# STM32F103RCT6.net
KiCad netlist of a schematic drawn in EasyEDA Pro
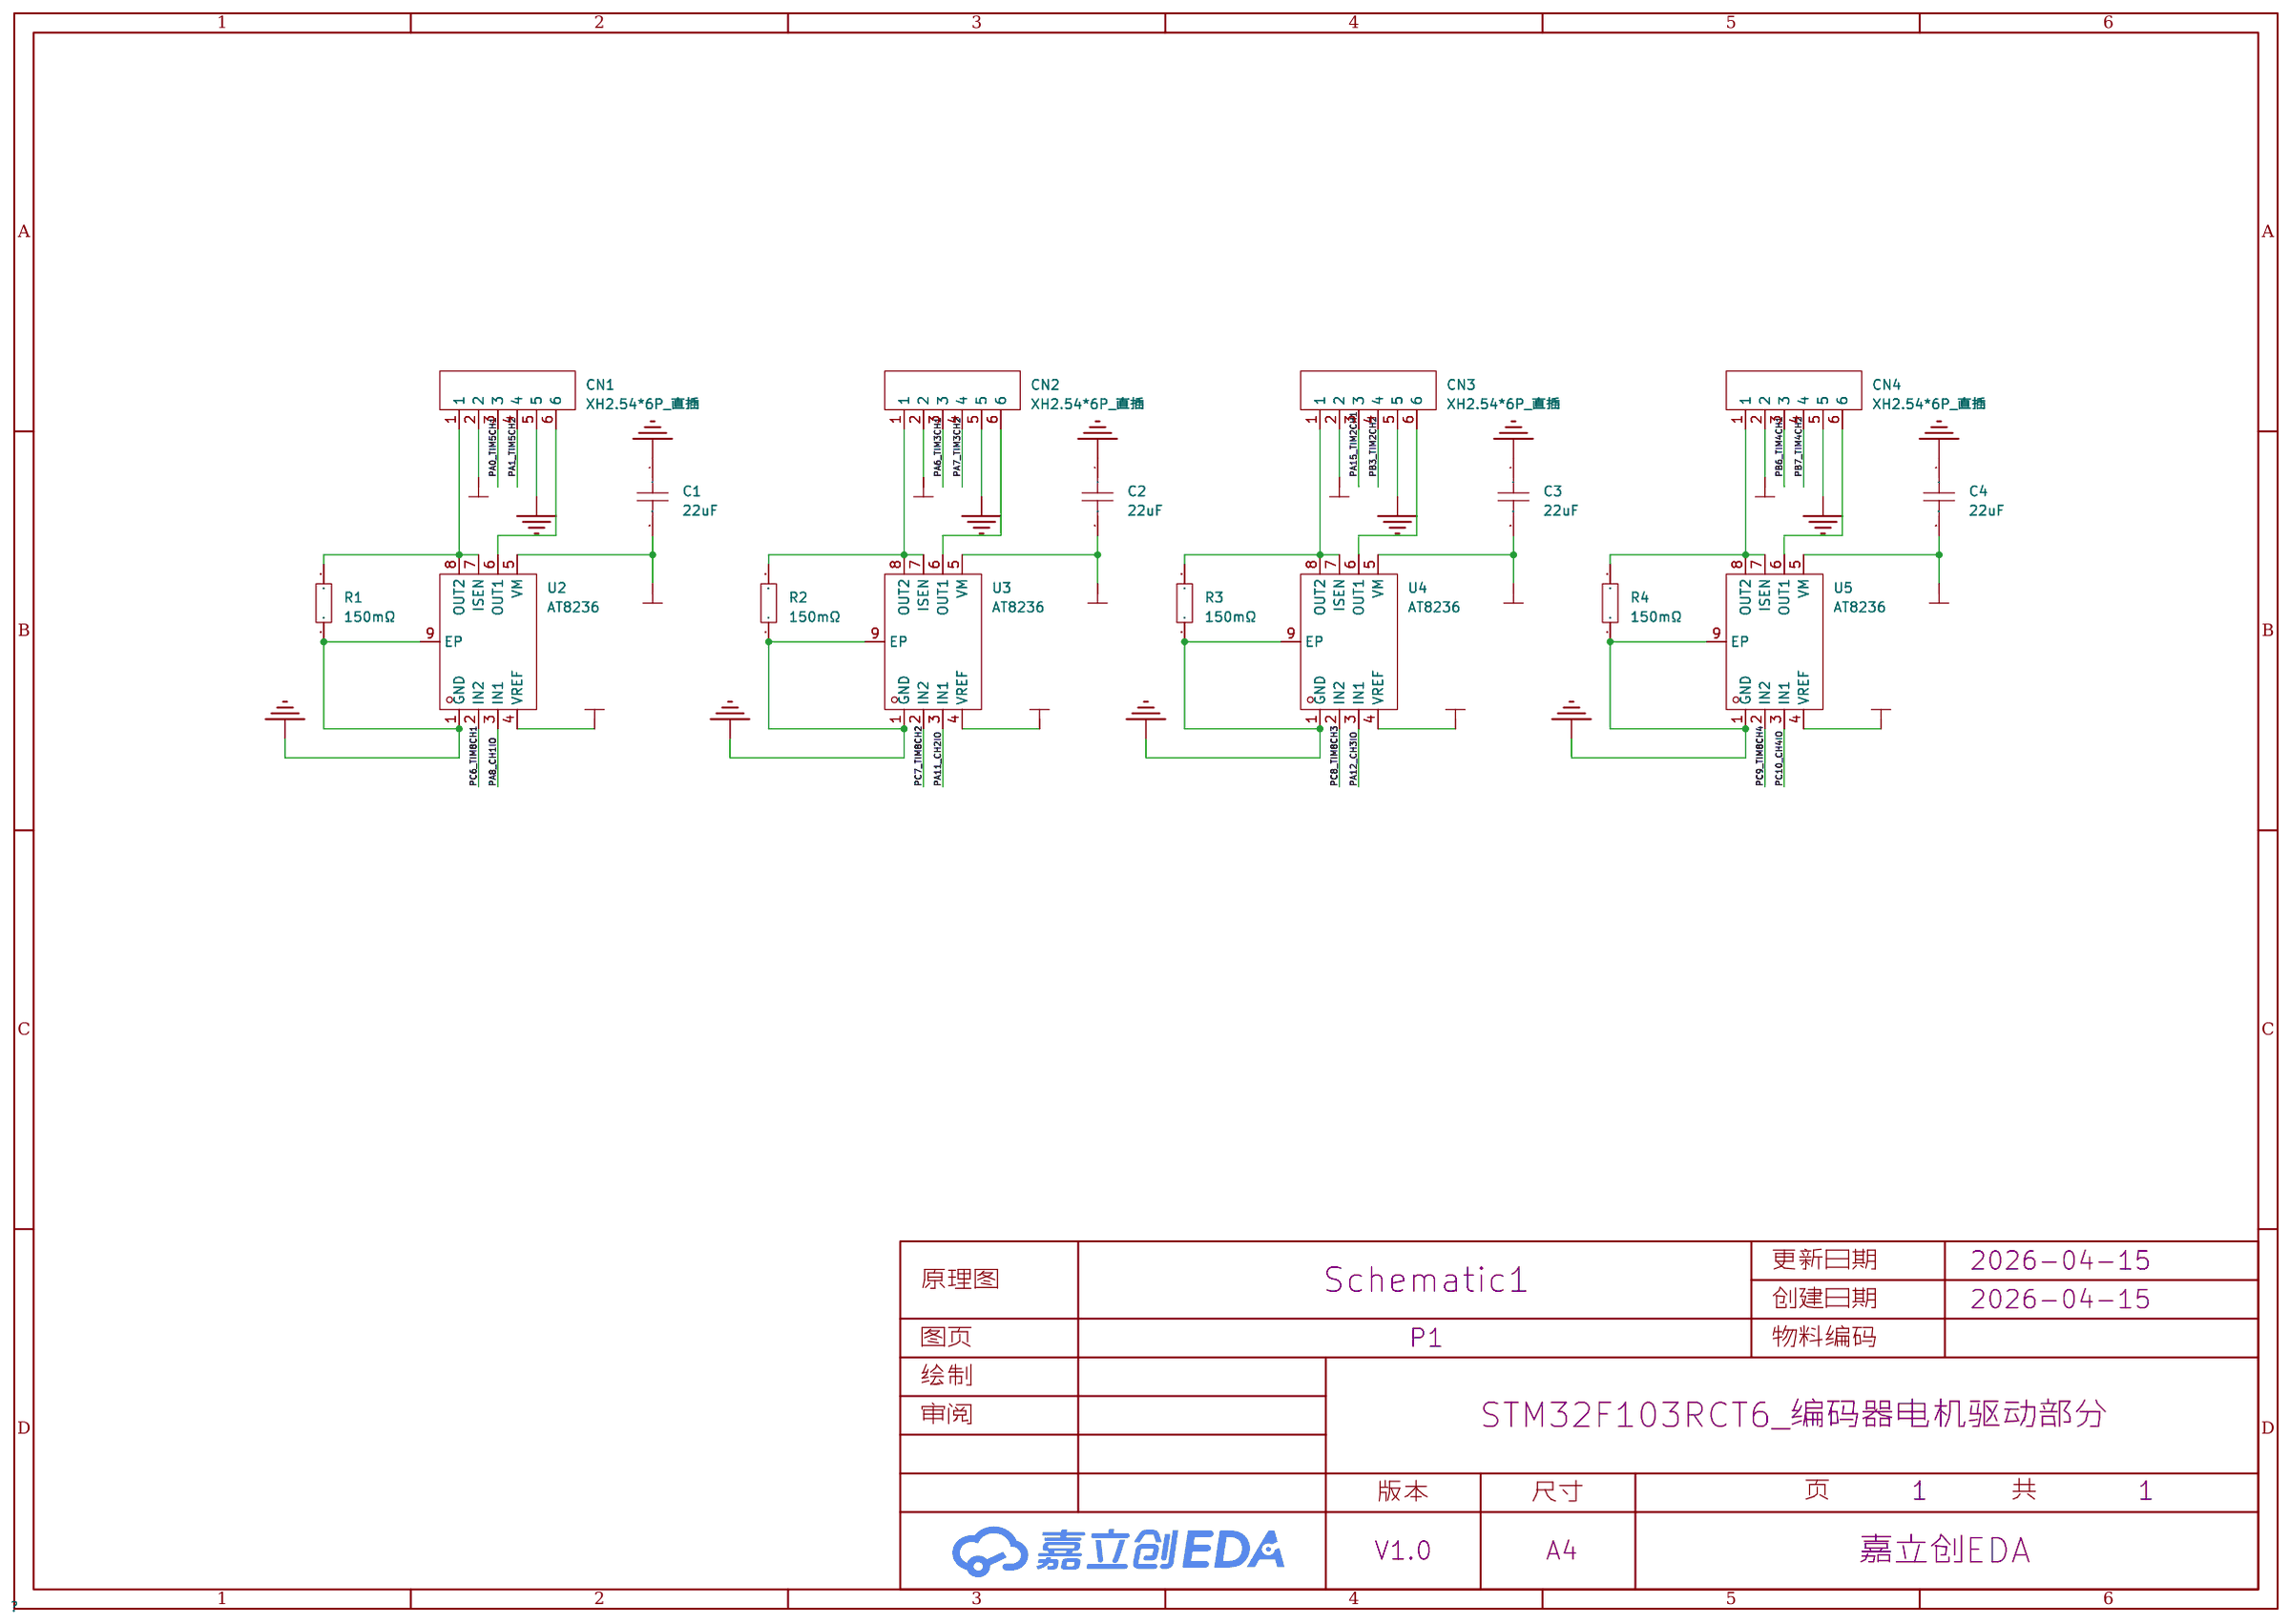
[diagram p0: schematic sheet]

(export (version "E")
  (design (tool "Eeschema 10.0.6"))
  (components
    (comp (ref "C1")
      (value "22uF")
      (footprint "easyedapro:C0603")
      (libsource (lib "easyedapro") (part "Capacitance"))
    )
    (comp (ref "C2")
      (value "22uF")
      (footprint "easyedapro:C0603")
      (libsource (lib "easyedapro") (part "Capacitance"))
    )
    (comp (ref "C3")
      (value "22uF")
      (footprint "easyedapro:C0603")
      (libsource (lib "easyedapro") (part "Capacitance"))
    )
    (comp (ref "C4")
      (value "22uF")
      (footprint "easyedapro:C0603")
      (libsource (lib "easyedapro") (part "Capacitance"))
    )
    (comp (ref "CN1")
      (value "XH2.54*6P_直插")
      (footprint "easyedapro:CONN-TH_XH2.54-6P")
      (libsource (lib "easyedapro") (part "XH2.54*6P_直插"))
    )
    (comp (ref "CN2")
      (value "XH2.54*6P_直插")
      (footprint "easyedapro:CONN-TH_XH2.54-6P")
      (libsource (lib "easyedapro") (part "XH2.54*6P_直插"))
    )
    (comp (ref "CN3")
      (value "XH2.54*6P_直插")
      (footprint "easyedapro:CONN-TH_XH2.54-6P")
      (libsource (lib "easyedapro") (part "XH2.54*6P_直插"))
    )
    (comp (ref "CN4")
      (value "XH2.54*6P_直插")
      (footprint "easyedapro:CONN-TH_XH2.54-6P")
      (libsource (lib "easyedapro") (part "XH2.54*6P_直插"))
    )
    (comp (ref "R1")
      (value "150mΩ")
      (footprint "easyedapro:R0603")
      (libsource (lib "easyedapro") (part "电阻"))
    )
    (comp (ref "R2")
      (value "150mΩ")
      (footprint "easyedapro:R0603")
      (libsource (lib "easyedapro") (part "电阻"))
    )
    (comp (ref "R3")
      (value "150mΩ")
      (footprint "easyedapro:R0603")
      (libsource (lib "easyedapro") (part "电阻"))
    )
    (comp (ref "R4")
      (value "150mΩ")
      (footprint "easyedapro:R0603")
      (libsource (lib "easyedapro") (part "电阻"))
    )
    (comp (ref "U2")
      (value "AT8236")
      (footprint "easyedapro:ESOP-8_L4.9-W3.9-P1.27-LS6.0-BL-EP")
      (fields (field (name "Manufacturer") "杭州中科微"))
      (libsource (lib "easyedapro") (part "AT8236"))
    )
    (comp (ref "U3")
      (value "AT8236")
      (footprint "easyedapro:ESOP-8_L4.9-W3.9-P1.27-LS6.0-BL-EP")
      (fields (field (name "Manufacturer") "杭州中科微"))
      (libsource (lib "easyedapro") (part "AT8236"))
    )
    (comp (ref "U4")
      (value "AT8236")
      (footprint "easyedapro:ESOP-8_L4.9-W3.9-P1.27-LS6.0-BL-EP")
      (fields (field (name "Manufacturer") "杭州中科微"))
      (libsource (lib "easyedapro") (part "AT8236"))
    )
    (comp (ref "U5")
      (value "AT8236")
      (footprint "easyedapro:ESOP-8_L4.9-W3.9-P1.27-LS6.0-BL-EP")
      (fields (field (name "Manufacturer") "杭州中科微"))
      (libsource (lib "easyedapro") (part "AT8236"))
    )
  )
  (nets
    (net (code "1") (name "+3V3") (class "Default")
      (node (ref "U2") (pin "4") (pinfunction "VREF_4") (pintype "unspecified"))
      (node (ref "U3") (pin "4") (pinfunction "VREF_4") (pintype "unspecified"))
      (node (ref "U4") (pin "4") (pinfunction "VREF_4") (pintype "unspecified"))
      (node (ref "U5") (pin "4") (pinfunction "VREF_4") (pintype "unspecified"))
    )
    (net (code "2") (name "/PA0_TIM5CH1") (class "Default")
      (node (ref "CN1") (pin "3") (pinfunction "3_3") (pintype "unspecified"))
    )
    (net (code "3") (name "/PA1_TIM5CH2") (class "Default")
      (node (ref "CN1") (pin "4") (pinfunction "4_4") (pintype "unspecified"))
    )
    (net (code "4") (name "/PA6_TIM3CH1") (class "Default")
      (node (ref "CN2") (pin "3") (pinfunction "3_3") (pintype "unspecified"))
    )
    (net (code "5") (name "/PA7_TIM3CH2") (class "Default")
      (node (ref "CN2") (pin "4") (pinfunction "4_4") (pintype "unspecified"))
    )
    (net (code "6") (name "/PA8_CH1IO") (class "Default")
      (node (ref "U2") (pin "3") (pinfunction "IN1_3") (pintype "unspecified"))
    )
    (net (code "7") (name "/PA11_CH2IO") (class "Default")
      (node (ref "U3") (pin "3") (pinfunction "IN1_3") (pintype "unspecified"))
    )
    (net (code "8") (name "/PA12_CH3IO") (class "Default")
      (node (ref "U4") (pin "3") (pinfunction "IN1_3") (pintype "unspecified"))
    )
    (net (code "9") (name "/PA15_TIM2CH1") (class "Default")
      (node (ref "CN3") (pin "3") (pinfunction "3_3") (pintype "unspecified"))
    )
    (net (code "10") (name "/PB3_TIM2CH2") (class "Default")
      (node (ref "CN3") (pin "4") (pinfunction "4_4") (pintype "unspecified"))
    )
    (net (code "11") (name "/PB6_TIM4CH1") (class "Default")
      (node (ref "CN4") (pin "3") (pinfunction "3_3") (pintype "unspecified"))
    )
    (net (code "12") (name "/PB7_TIM4CH2") (class "Default")
      (node (ref "CN4") (pin "4") (pinfunction "4_4") (pintype "unspecified"))
    )
    (net (code "13") (name "/PC6_TIM8CH1") (class "Default")
      (node (ref "U2") (pin "2") (pinfunction "IN2_2") (pintype "unspecified"))
    )
    (net (code "14") (name "/PC7_TIM8CH2") (class "Default")
      (node (ref "U3") (pin "2") (pinfunction "IN2_2") (pintype "unspecified"))
    )
    (net (code "15") (name "/PC8_TIM8CH3") (class "Default")
      (node (ref "U4") (pin "2") (pinfunction "IN2_2") (pintype "unspecified"))
    )
    (net (code "16") (name "/PC9_TIM8CH4") (class "Default")
      (node (ref "U5") (pin "2") (pinfunction "IN2_2") (pintype "unspecified"))
    )
    (net (code "17") (name "/PC10_CH4IO") (class "Default")
      (node (ref "U5") (pin "3") (pinfunction "IN1_3") (pintype "unspecified"))
    )
    (net (code "18") (name "GND") (class "Default")
      (node (ref "CN1") (pin "5") (pinfunction "5_5") (pintype "unspecified"))
      (node (ref "CN2") (pin "5") (pinfunction "5_5") (pintype "unspecified"))
      (node (ref "CN3") (pin "5") (pinfunction "5_5") (pintype "unspecified"))
      (node (ref "CN4") (pin "5") (pinfunction "5_5") (pintype "unspecified"))
    )
    (net (code "19") (name "Net-(U2-ISEN)") (class "Default")
      (node (ref "CN1") (pin "1") (pinfunction "1_1") (pintype "unspecified"))
      (node (ref "R1") (pin "2") (pinfunction "2_2") (pintype "input"))
      (node (ref "U2") (pin "7") (pinfunction "ISEN_7") (pintype "unspecified"))
      (node (ref "U2") (pin "8") (pinfunction "OUT2_8") (pintype "unspecified"))
    )
    (net (code "20") (name "Net-(U2-OUT1)") (class "Default")
      (node (ref "CN1") (pin "6") (pinfunction "6_6") (pintype "unspecified"))
      (node (ref "U2") (pin "6") (pinfunction "OUT1_6") (pintype "unspecified"))
    )
    (net (code "21") (name "Net-(U3-ISEN)") (class "Default")
      (node (ref "CN2") (pin "1") (pinfunction "1_1") (pintype "unspecified"))
      (node (ref "R2") (pin "2") (pinfunction "2_2") (pintype "input"))
      (node (ref "U3") (pin "7") (pinfunction "ISEN_7") (pintype "unspecified"))
      (node (ref "U3") (pin "8") (pinfunction "OUT2_8") (pintype "unspecified"))
    )
    (net (code "22") (name "Net-(U3-OUT1)") (class "Default")
      (node (ref "CN2") (pin "6") (pinfunction "6_6") (pintype "unspecified"))
      (node (ref "U3") (pin "6") (pinfunction "OUT1_6") (pintype "unspecified"))
    )
    (net (code "23") (name "Net-(U4-ISEN)") (class "Default")
      (node (ref "CN3") (pin "1") (pinfunction "1_1") (pintype "unspecified"))
      (node (ref "R3") (pin "2") (pinfunction "2_2") (pintype "input"))
      (node (ref "U4") (pin "7") (pinfunction "ISEN_7") (pintype "unspecified"))
      (node (ref "U4") (pin "8") (pinfunction "OUT2_8") (pintype "unspecified"))
    )
    (net (code "24") (name "Net-(U4-OUT1)") (class "Default")
      (node (ref "CN3") (pin "6") (pinfunction "6_6") (pintype "unspecified"))
      (node (ref "U4") (pin "6") (pinfunction "OUT1_6") (pintype "unspecified"))
    )
    (net (code "25") (name "Net-(U5-ISEN)") (class "Default")
      (node (ref "CN4") (pin "1") (pinfunction "1_1") (pintype "unspecified"))
      (node (ref "R4") (pin "2") (pinfunction "2_2") (pintype "input"))
      (node (ref "U5") (pin "7") (pinfunction "ISEN_7") (pintype "unspecified"))
      (node (ref "U5") (pin "8") (pinfunction "OUT2_8") (pintype "unspecified"))
    )
    (net (code "26") (name "Net-(U5-OUT1)") (class "Default")
      (node (ref "CN4") (pin "6") (pinfunction "6_6") (pintype "unspecified"))
      (node (ref "U5") (pin "6") (pinfunction "OUT1_6") (pintype "unspecified"))
    )
    (net (code "27") (name "PGND") (class "Default")
      (node (ref "C1") (pin "1") (pinfunction "1_1") (pintype "input"))
      (node (ref "C2") (pin "1") (pinfunction "1_1") (pintype "input"))
      (node (ref "C3") (pin "1") (pinfunction "1_1") (pintype "input"))
      (node (ref "C4") (pin "1") (pinfunction "1_1") (pintype "input"))
      (node (ref "R1") (pin "1") (pinfunction "1_1") (pintype "input"))
      (node (ref "R2") (pin "1") (pinfunction "1_1") (pintype "input"))
      (node (ref "R3") (pin "1") (pinfunction "1_1") (pintype "input"))
      (node (ref "R4") (pin "1") (pinfunction "1_1") (pintype "input"))
      (node (ref "U2") (pin "1") (pinfunction "GND_1") (pintype "unspecified"))
      (node (ref "U2") (pin "9") (pinfunction "EP_9") (pintype "unspecified"))
      (node (ref "U3") (pin "1") (pinfunction "GND_1") (pintype "unspecified"))
      (node (ref "U3") (pin "9") (pinfunction "EP_9") (pintype "unspecified"))
      (node (ref "U4") (pin "1") (pinfunction "GND_1") (pintype "unspecified"))
      (node (ref "U4") (pin "9") (pinfunction "EP_9") (pintype "unspecified"))
      (node (ref "U5") (pin "1") (pinfunction "GND_1") (pintype "unspecified"))
      (node (ref "U5") (pin "9") (pinfunction "EP_9") (pintype "unspecified"))
    )
    (net (code "28") (name "VCC_5V") (class "Default")
      (node (ref "CN1") (pin "2") (pinfunction "2_2") (pintype "unspecified"))
      (node (ref "CN2") (pin "2") (pinfunction "2_2") (pintype "unspecified"))
      (node (ref "CN3") (pin "2") (pinfunction "2_2") (pintype "unspecified"))
      (node (ref "CN4") (pin "2") (pinfunction "2_2") (pintype "unspecified"))
    )
    (net (code "29") (name "VIN") (class "Default")
      (node (ref "C1") (pin "2") (pinfunction "2_2") (pintype "input"))
      (node (ref "C2") (pin "2") (pinfunction "2_2") (pintype "input"))
      (node (ref "C3") (pin "2") (pinfunction "2_2") (pintype "input"))
      (node (ref "C4") (pin "2") (pinfunction "2_2") (pintype "input"))
      (node (ref "U2") (pin "5") (pinfunction "VM_5") (pintype "unspecified"))
      (node (ref "U3") (pin "5") (pinfunction "VM_5") (pintype "unspecified"))
      (node (ref "U4") (pin "5") (pinfunction "VM_5") (pintype "unspecified"))
      (node (ref "U5") (pin "5") (pinfunction "VM_5") (pintype "unspecified"))
    )
  )
)
